# MOSFET_out.net
KiCad netlist of a schematic drawn in Altium Designer
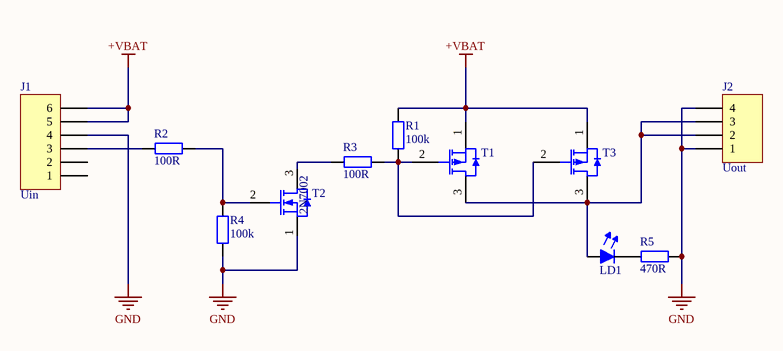
[diagram p0: MOSFET out.SchDoc]

(export (version "E")
  (design (tool "Eeschema 10.0.6"))
  (components
    (comp (ref "J1")
      (value "Uin")
      (footprint "HDR1X6")
      (description "Header, 6-Pin")
      (fields (field (name "PUBLISHER") "Altium Limited"))
      (libsource (lib "Miscellaneous Connectors") (part "Header 6"))
    )
    (comp (ref "J2")
      (value "Uout")
      (footprint "HDR1X4")
      (description "Header, 4-Pin")
      (fields (field (name "PUBLISHER") "Altium Limited"))
      (libsource (lib "Miscellaneous Connectors") (part "Header 4"))
    )
    (comp (ref "LD1")
      (value "LED diode")
      (footprint "LED_0603")
      (description "LED blue")
      (libsource (lib "IKSOR_LIB_main") (part "LED diode"))
    )
    (comp (ref "R1")
      (value "100k")
      (footprint "0603 RES")
      (description "Resistor SMD")
      (fields (field (name "Comment") "Resistor generic"))
      (libsource (lib "IKSOR_LIB_main") (part "Resistor"))
    )
    (comp (ref "R2")
      (value "100R")
      (footprint "0603 RES")
      (description "Resistor SMD")
      (fields (field (name "Comment") "Resistor generic"))
      (libsource (lib "IKSOR_LIB_main") (part "Resistor"))
    )
    (comp (ref "R3")
      (value "100R")
      (footprint "0603 RES")
      (description "Resistor SMD")
      (fields (field (name "Comment") "Resistor generic"))
      (libsource (lib "IKSOR_LIB_main") (part "Resistor"))
    )
    (comp (ref "R4")
      (value "100k")
      (footprint "0603 RES")
      (description "Resistor SMD")
      (fields (field (name "Comment") "Resistor generic"))
      (libsource (lib "IKSOR_LIB_main") (part "Resistor"))
    )
    (comp (ref "R5")
      (value "470R")
      (footprint "0603 RES")
      (description "Resistor SMD")
      (fields (field (name "Comment") "Resistor generic"))
      (libsource (lib "IKSOR_LIB_main") (part "Resistor"))
    )
    (comp (ref "T1")
      (value "MOSFET-P")
      (footprint "TDSON-8")
      (description "MOSFET P")
      (fields (field (name "VOLTAGE") "-30V"))
      (libsource (lib "IKSOR_LIB_main") (part "MOSFET-P"))
    )
    (comp (ref "T2")
      (value "2N7002")
      (footprint "SOT23")
      (description "MOSFET N")
      (fields (field (name "VOLTAGE") "20V") (field (name "Comment") "MOSFET-N"))
      (libsource (lib "IKSOR_LIB_main") (part "MOSFET-N"))
    )
    (comp (ref "T3")
      (value "MOSFET-P")
      (footprint "TDSON-8")
      (description "MOSFET P")
      (fields (field (name "VOLTAGE") "-30V"))
      (libsource (lib "IKSOR_LIB_main") (part "MOSFET-P"))
    )
  )
  (nets
    (net (code "1") (name "+VBAT") (class "Default")
      (node (ref "J1") (pin "5") (pinfunction "5_5") (pintype "passive"))
      (node (ref "J1") (pin "6") (pinfunction "6_6") (pintype "passive"))
      (node (ref "R1") (pin "2") (pinfunction "2_2") (pintype "passive"))
      (node (ref "T1") (pin "1") (pinfunction "D_1") (pintype "passive"))
      (node (ref "T3") (pin "1") (pinfunction "D_1") (pintype "passive"))
    )
    (net (code "2") (name "GND") (class "Default")
      (node (ref "J1") (pin "4") (pinfunction "4_4") (pintype "passive"))
      (node (ref "J2") (pin "1") (pinfunction "1_1") (pintype "passive"))
      (node (ref "J2") (pin "4") (pinfunction "4_4") (pintype "passive"))
      (node (ref "R4") (pin "2") (pinfunction "2_2") (pintype "passive"))
      (node (ref "R5") (pin "1") (pinfunction "1_1") (pintype "passive"))
      (node (ref "T2") (pin "1") (pinfunction "S_1") (pintype "passive"))
    )
    (net (code "3") (name "Net-(J1-Pad3)") (class "Default")
      (node (ref "J1") (pin "3") (pinfunction "3_3") (pintype "passive"))
      (node (ref "R2") (pin "2") (pinfunction "2_2") (pintype "passive"))
    )
    (net (code "4") (name "Net-(LD1-A1)") (class "Default")
      (node (ref "J2") (pin "2") (pinfunction "2_2") (pintype "passive"))
      (node (ref "J2") (pin "3") (pinfunction "3_3") (pintype "passive"))
      (node (ref "LD1") (pin "1") (pinfunction "A1_1") (pintype "passive"))
      (node (ref "T1") (pin "3") (pinfunction "S_3") (pintype "passive"))
      (node (ref "T3") (pin "3") (pinfunction "S_3") (pintype "passive"))
    )
    (net (code "5") (name "Net-(LD1-K)") (class "Default")
      (node (ref "LD1") (pin "2") (pinfunction "K_2") (pintype "passive"))
      (node (ref "R5") (pin "2") (pinfunction "2_2") (pintype "passive"))
    )
    (net (code "6") (name "Net-(T1-G)") (class "Default")
      (node (ref "R1") (pin "1") (pinfunction "1_1") (pintype "passive"))
      (node (ref "R3") (pin "1") (pinfunction "1_1") (pintype "passive"))
      (node (ref "T1") (pin "2") (pinfunction "G_2") (pintype "passive"))
      (node (ref "T3") (pin "2") (pinfunction "G_2") (pintype "passive"))
    )
    (net (code "7") (name "Net-(T2-D)") (class "Default")
      (node (ref "R3") (pin "2") (pinfunction "2_2") (pintype "passive"))
      (node (ref "T2") (pin "3") (pinfunction "D_3") (pintype "passive"))
    )
    (net (code "8") (name "Net-(T2-G)") (class "Default")
      (node (ref "R2") (pin "1") (pinfunction "1_1") (pintype "passive"))
      (node (ref "R4") (pin "1") (pinfunction "1_1") (pintype "passive"))
      (node (ref "T2") (pin "2") (pinfunction "G_2") (pintype "passive"))
    )
    (net (code "9") (name "unconnected-(J1-Pad1)") (class "Default")
      (node (ref "J1") (pin "1") (pinfunction "1_1") (pintype "passive"))
    )
    (net (code "10") (name "unconnected-(J1-Pad2)") (class "Default")
      (node (ref "J1") (pin "2") (pinfunction "2_2") (pintype "passive"))
    )
  )
)
